# breakout.net
KiCad netlist of a schematic drawn in EAGLE
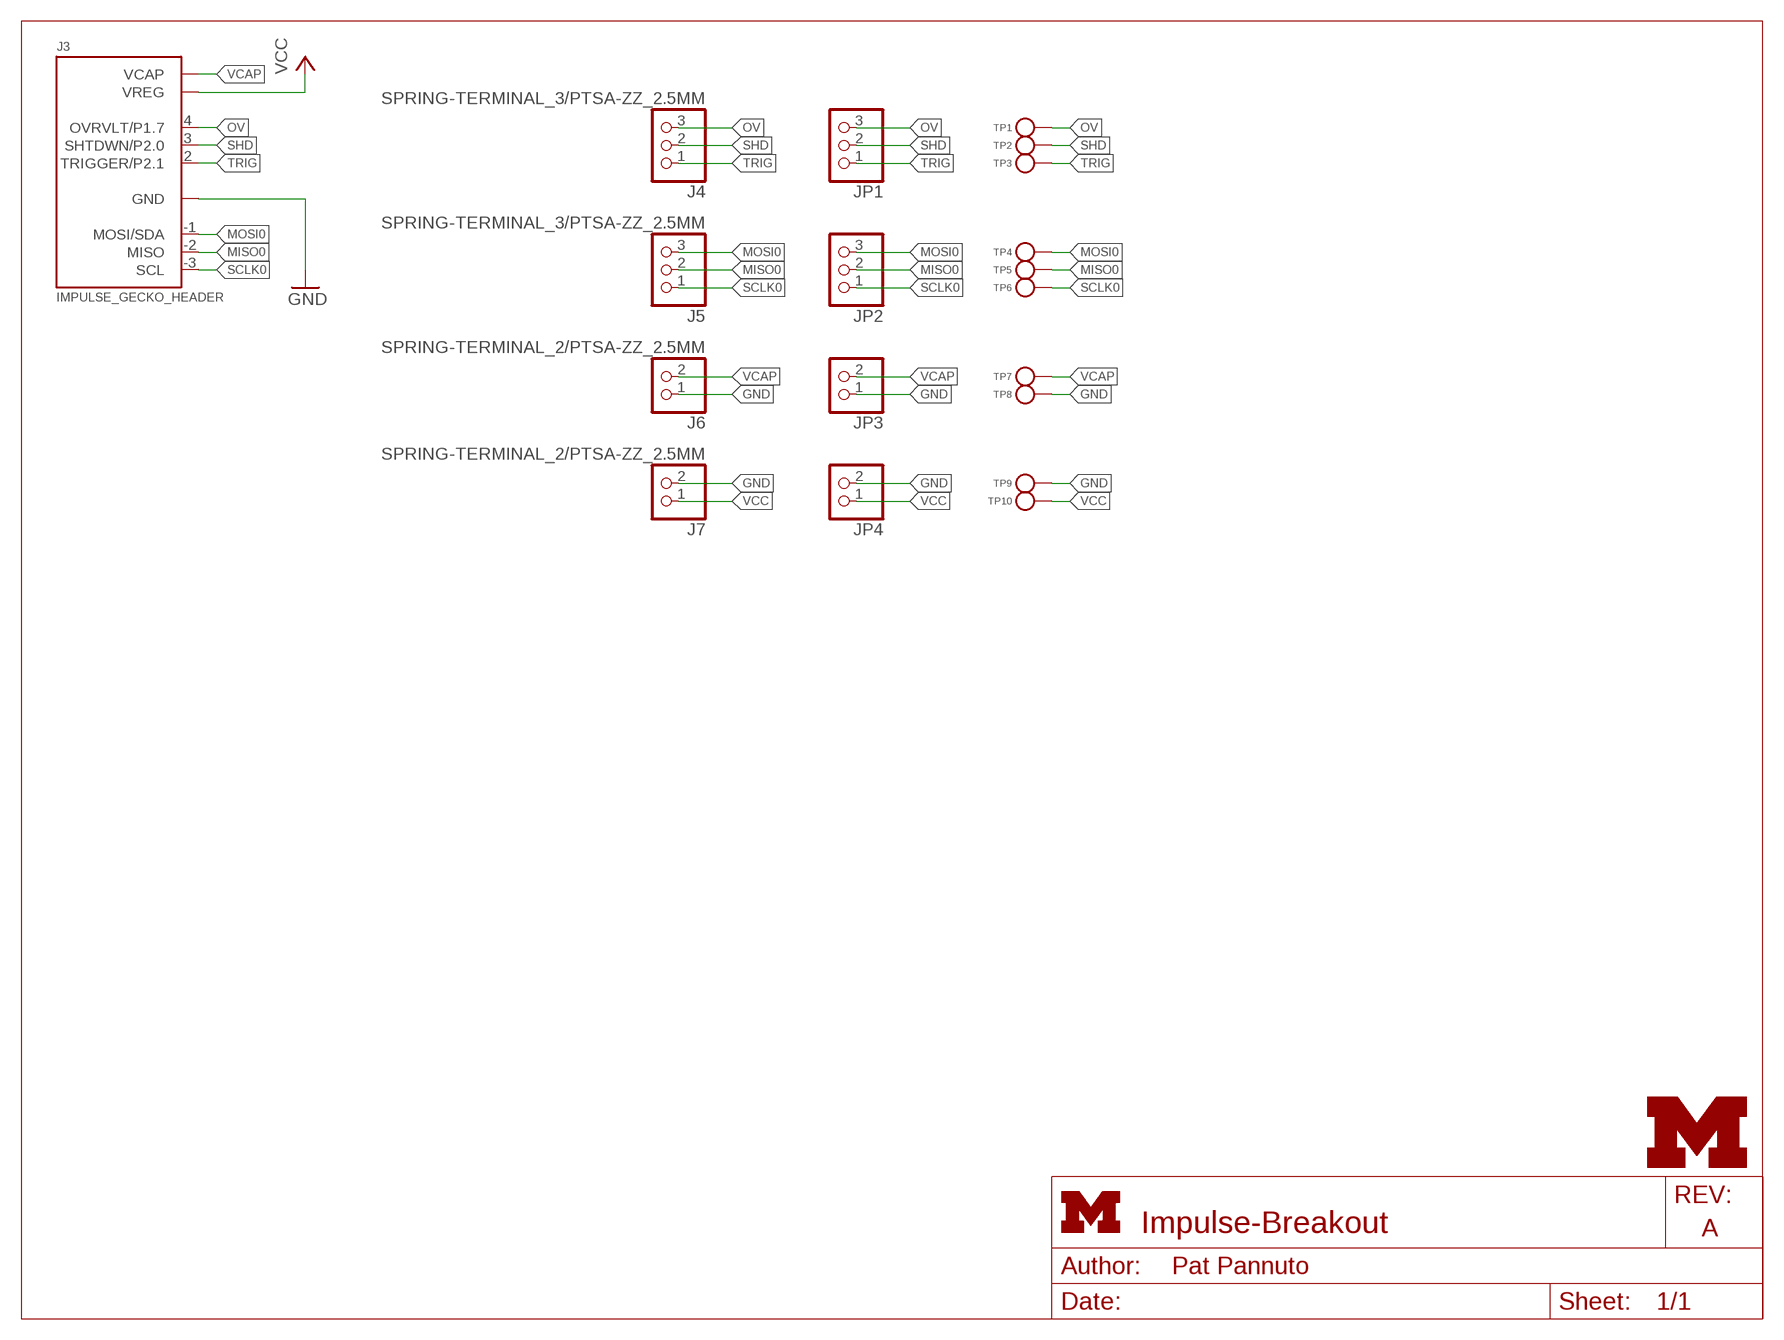
[diagram p0: schematic, sheet 1]

(export (version "E")
  (design (tool "Eeschema 10.0.6"))
  (components
    (comp (ref "J3")
      (value "IMPULSE_GECKO_HEADER")
      (footprint "eagle-import:HEADER1X9_0.05IN")
      (libsource (lib "eagle-import") (part "IMPULSE_GECKO_HEADER"))
    )
    (comp (ref "J4")
      (value "SPRING-TERMINAL_3/PTSA-ZZ_2.5MM")
      (footprint "eagle-import:1X3_PTSA-ZZ_2.5MM")
      (libsource (lib "eagle-import") (part "SPRING-TERMINAL_3/PTSA-ZZ_2.5MM"))
    )
    (comp (ref "J5")
      (value "SPRING-TERMINAL_3/PTSA-ZZ_2.5MM")
      (footprint "eagle-import:1X3_PTSA-ZZ_2.5MM")
      (libsource (lib "eagle-import") (part "SPRING-TERMINAL_3/PTSA-ZZ_2.5MM"))
    )
    (comp (ref "J6")
      (value "SPRING-TERMINAL_2/PTSA-ZZ_2.5MM")
      (footprint "eagle-import:1X2_PTSA-ZZ_2.5MM")
      (libsource (lib "eagle-import") (part "SPRING-TERMINAL_2/PTSA-ZZ_2.5MM"))
    )
    (comp (ref "J7")
      (value "SPRING-TERMINAL_2/PTSA-ZZ_2.5MM")
      (footprint "eagle-import:1X2_PTSA-ZZ_2.5MM")
      (libsource (lib "eagle-import") (part "SPRING-TERMINAL_2/PTSA-ZZ_2.5MM"))
    )
    (comp (ref "JP1")
      (value "PINHD-1X3")
      (footprint "eagle-import:1X03")
      (libsource (lib "eagle-import") (part "PINHD-1X3"))
    )
    (comp (ref "JP2")
      (value "PINHD-1X3")
      (footprint "eagle-import:1X03")
      (libsource (lib "eagle-import") (part "PINHD-1X3"))
    )
    (comp (ref "JP3")
      (value "PINHD-1X2")
      (footprint "eagle-import:1X02")
      (libsource (lib "eagle-import") (part "PINHD-1X2"))
    )
    (comp (ref "JP4")
      (value "PINHD-1X2")
      (footprint "eagle-import:1X02")
      (libsource (lib "eagle-import") (part "PINHD-1X2"))
    )
    (comp (ref "TP1")
      (value "TEST_POINT_0.040IN")
      (footprint "eagle-import:TESTPOINT_0.040IN")
      (libsource (lib "eagle-import") (part "TEST_POINT_0.040IN"))
    )
    (comp (ref "TP2")
      (value "TEST_POINT_0.040IN")
      (footprint "eagle-import:TESTPOINT_0.040IN")
      (libsource (lib "eagle-import") (part "TEST_POINT_0.040IN"))
    )
    (comp (ref "TP3")
      (value "TEST_POINT_0.040IN")
      (footprint "eagle-import:TESTPOINT_0.040IN")
      (libsource (lib "eagle-import") (part "TEST_POINT_0.040IN"))
    )
    (comp (ref "TP4")
      (value "TEST_POINT_0.040IN")
      (footprint "eagle-import:TESTPOINT_0.040IN")
      (libsource (lib "eagle-import") (part "TEST_POINT_0.040IN"))
    )
    (comp (ref "TP5")
      (value "TEST_POINT_0.040IN")
      (footprint "eagle-import:TESTPOINT_0.040IN")
      (libsource (lib "eagle-import") (part "TEST_POINT_0.040IN"))
    )
    (comp (ref "TP6")
      (value "TEST_POINT_0.040IN")
      (footprint "eagle-import:TESTPOINT_0.040IN")
      (libsource (lib "eagle-import") (part "TEST_POINT_0.040IN"))
    )
    (comp (ref "TP7")
      (value "TEST_POINT_0.040IN")
      (footprint "eagle-import:TESTPOINT_0.040IN")
      (libsource (lib "eagle-import") (part "TEST_POINT_0.040IN"))
    )
    (comp (ref "TP8")
      (value "TEST_POINT_0.040IN")
      (footprint "eagle-import:TESTPOINT_0.040IN")
      (libsource (lib "eagle-import") (part "TEST_POINT_0.040IN"))
    )
    (comp (ref "TP9")
      (value "TEST_POINT_0.040IN")
      (footprint "eagle-import:TESTPOINT_0.040IN")
      (libsource (lib "eagle-import") (part "TEST_POINT_0.040IN"))
    )
    (comp (ref "TP10")
      (value "TEST_POINT_0.040IN")
      (footprint "eagle-import:TESTPOINT_0.040IN")
      (libsource (lib "eagle-import") (part "TEST_POINT_0.040IN"))
    )
    (comp (ref "U$1")
      (value "UMICH_SOLID_SMALL")
      (footprint "eagle-import:UMICH_SOLID_75MIL")
      (libsource (lib "eagle-import") (part "UMICH_SOLID_SMALL"))
    )
  )
  (nets
    (net (code "1") (name "GND") (class "Default")
      (node (ref "J3") (pin "0") (pinfunction "GND_0") (pintype "bidirectional"))
      (node (ref "J6") (pin "1") (pinfunction "1_1") (pintype "passive"))
      (node (ref "J7") (pin "2") (pinfunction "2_2") (pintype "passive"))
      (node (ref "JP3") (pin "1") (pinfunction "1_1") (pintype "passive"))
      (node (ref "JP4") (pin "2") (pinfunction "2_2") (pintype "passive"))
      (node (ref "TP8") (pin "TESTPOINT") (pinfunction "TESTPOINT_TESTPOINT") (pintype "bidirectional"))
      (node (ref "TP9") (pin "TESTPOINT") (pinfunction "TESTPOINT_TESTPOINT") (pintype "bidirectional"))
    )
    (net (code "2") (name "MISO0") (class "Default")
      (node (ref "J3") (pin "-2") (pinfunction "MISO_-2") (pintype "bidirectional"))
      (node (ref "J5") (pin "2") (pinfunction "2_2") (pintype "passive"))
      (node (ref "JP2") (pin "2") (pinfunction "2_2") (pintype "passive"))
      (node (ref "TP5") (pin "TESTPOINT") (pinfunction "TESTPOINT_TESTPOINT") (pintype "bidirectional"))
    )
    (net (code "3") (name "MOSI0") (class "Default")
      (node (ref "J3") (pin "-1") (pinfunction "MOSI/SDA_-1") (pintype "bidirectional"))
      (node (ref "J5") (pin "3") (pinfunction "3_3") (pintype "passive"))
      (node (ref "JP2") (pin "3") (pinfunction "3_3") (pintype "passive"))
      (node (ref "TP4") (pin "TESTPOINT") (pinfunction "TESTPOINT_TESTPOINT") (pintype "bidirectional"))
    )
    (net (code "4") (name "OV") (class "Default")
      (node (ref "J3") (pin "4") (pinfunction "OVRVLT/P1.7_4") (pintype "bidirectional"))
      (node (ref "J4") (pin "3") (pinfunction "3_3") (pintype "passive"))
      (node (ref "JP1") (pin "3") (pinfunction "3_3") (pintype "passive"))
      (node (ref "TP1") (pin "TESTPOINT") (pinfunction "TESTPOINT_TESTPOINT") (pintype "bidirectional"))
    )
    (net (code "5") (name "SCLK0") (class "Default")
      (node (ref "J3") (pin "-3") (pinfunction "SCL_-3") (pintype "bidirectional"))
      (node (ref "J5") (pin "1") (pinfunction "1_1") (pintype "passive"))
      (node (ref "JP2") (pin "1") (pinfunction "1_1") (pintype "passive"))
      (node (ref "TP6") (pin "TESTPOINT") (pinfunction "TESTPOINT_TESTPOINT") (pintype "bidirectional"))
    )
    (net (code "6") (name "SHD") (class "Default")
      (node (ref "J3") (pin "3") (pinfunction "SHTDWN/P2.0_3") (pintype "bidirectional"))
      (node (ref "J4") (pin "2") (pinfunction "2_2") (pintype "passive"))
      (node (ref "JP1") (pin "2") (pinfunction "2_2") (pintype "passive"))
      (node (ref "TP2") (pin "TESTPOINT") (pinfunction "TESTPOINT_TESTPOINT") (pintype "bidirectional"))
    )
    (net (code "7") (name "TRIG") (class "Default")
      (node (ref "J3") (pin "2") (pinfunction "TRIGGER/P2.1_2") (pintype "bidirectional"))
      (node (ref "J4") (pin "1") (pinfunction "1_1") (pintype "passive"))
      (node (ref "JP1") (pin "1") (pinfunction "1_1") (pintype "passive"))
      (node (ref "TP3") (pin "TESTPOINT") (pinfunction "TESTPOINT_TESTPOINT") (pintype "bidirectional"))
    )
    (net (code "8") (name "VCAP") (class "Default")
      (node (ref "J3") (pin "5") (pinfunction "VCAP_5") (pintype "output"))
      (node (ref "J6") (pin "2") (pinfunction "2_2") (pintype "passive"))
      (node (ref "JP3") (pin "2") (pinfunction "2_2") (pintype "passive"))
      (node (ref "TP7") (pin "TESTPOINT") (pinfunction "TESTPOINT_TESTPOINT") (pintype "bidirectional"))
    )
    (net (code "9") (name "VCC") (class "Default")
      (node (ref "J3") (pin "1") (pinfunction "VREG_1") (pintype "bidirectional"))
      (node (ref "J7") (pin "1") (pinfunction "1_1") (pintype "passive"))
      (node (ref "JP4") (pin "1") (pinfunction "1_1") (pintype "passive"))
      (node (ref "TP10") (pin "TESTPOINT") (pinfunction "TESTPOINT_TESTPOINT") (pintype "bidirectional"))
    )
  )
)
